# Module.net
KiCad netlist of a schematic drawn in Altium Designer
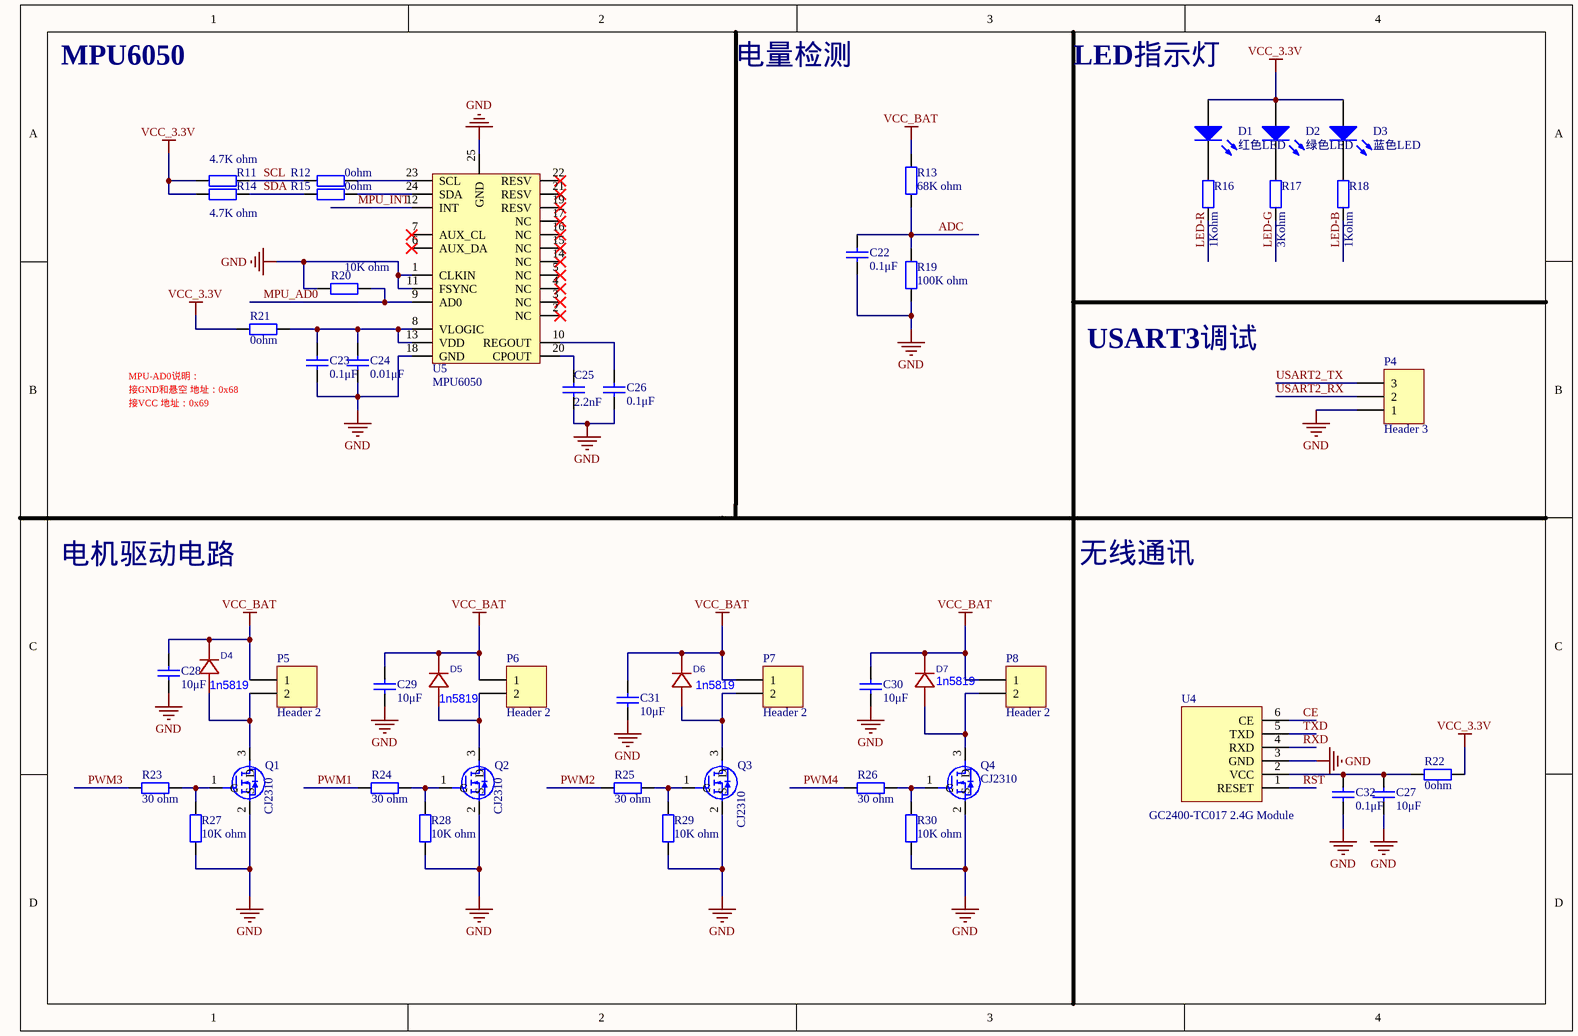
[diagram p0: Module.SchDoc]

(export (version "E")
  (design (tool "Eeschema 10.0.6"))
  (components
    (comp (ref "C22")
      (value "0.1μF")
      (footprint "0603C")
      (description "0.1μF_50V,X7R,±5%")
      (libsource (lib "Smart-Plane_1") (part "Cap_0.1μF_50V_0603"))
    )
    (comp (ref "C23")
      (value "0.1μF")
      (footprint "0603C")
      (description "0.1μF_50V,X7R,±5%")
      (libsource (lib "Smart-Plane_1") (part "Cap_0.1μF_50V_0603"))
    )
    (comp (ref "C24")
      (value "0.01μF")
      (footprint "0603C")
      (description "0.1μF_50V,X7R,±5%")
      (libsource (lib "Smart-Plane_1") (part "Cap_0.1μF_50V_0603"))
    )
    (comp (ref "C25")
      (value "2.2nF")
      (footprint "0603C")
      (description "10μF_35V,X5R,20%")
      (libsource (lib "Yang_Lib") (part "Cap_10μF_35V_0603"))
    )
    (comp (ref "C26")
      (value "0.1μF")
      (footprint "0603C")
      (description "0.1μF_50V,X7R,±5%")
      (libsource (lib "Smart-Plane_1") (part "Cap_0.1μF_50V_0603"))
    )
    (comp (ref "C27")
      (value "10μF")
      (footprint "0603C")
      (description "10μF_35V,X5R,20%")
      (libsource (lib "Yang_Lib") (part "Cap_10μF_35V_0603"))
    )
    (comp (ref "C28")
      (value "10μF")
      (footprint "0603C")
      (description "4.7μF_50V,±10%")
      (libsource (lib "Smart-Plane_1") (part "Cap_4.7μF_50V_0603"))
    )
    (comp (ref "C29")
      (value "10μF")
      (footprint "0603C")
      (description "4.7μF_50V,±10%")
      (libsource (lib "Smart-Plane_1") (part "Cap_4.7μF_50V_0603"))
    )
    (comp (ref "C30")
      (value "10μF")
      (footprint "0603C")
      (description "4.7μF_50V,±10%")
      (libsource (lib "Smart-Plane_1") (part "Cap_4.7μF_50V_0603"))
    )
    (comp (ref "C31")
      (value "10μF")
      (footprint "0603C")
      (description "4.7μF_50V,±10%")
      (libsource (lib "Smart-Plane_1") (part "Cap_4.7μF_50V_0603"))
    )
    (comp (ref "C32")
      (value "0.1μF")
      (footprint "0603C")
      (description "0.1μF_50V,X7R,±5%")
      (libsource (lib "Smart-Plane_1") (part "Cap_0.1μF_50V_0603"))
    )
    (comp (ref "D1")
      (value "红色LED")
      (footprint "0603LED")
      (description "蓝色LED")
      (libsource (lib "Smart-Plane_1") (part "蓝色LED"))
    )
    (comp (ref "D2")
      (value "绿色LED")
      (footprint "0603LED")
      (description "蓝色LED")
      (libsource (lib "Smart-Plane_1") (part "蓝色LED"))
    )
    (comp (ref "D3") (value "蓝色LED") (footprint "0603LED") (libsource (lib "Smart-Plane_1") (part "蓝色LED")))
    (comp (ref "D4")
      (value "1n5819")
      (footprint "0603R")
      (description "二极管配置:独立式;正向压降(Vf):600mV@200mA;直流反向耐压(Vr):40V;整流电流:350mA;")
      (fields (field (name "MANUFACTURER") "HXY MOSFET(华轩阳电子)") (field (name "MANUFACTURERPART") "1N5819WT"))
      (libsource (lib "Smart-Plane_1") (part "1n5819wt_c5451630"))
    )
    (comp (ref "D5")
      (value "1n5819")
      (footprint "0603R")
      (description "二极管配置:独立式;正向压降(Vf):600mV@200mA;直流反向耐压(Vr):40V;整流电流:350mA;")
      (fields (field (name "MANUFACTURER") "HXY MOSFET(华轩阳电子)") (field (name "MANUFACTURERPART") "1N5819WT"))
      (libsource (lib "Smart-Plane_1") (part "1n5819wt_c5451630"))
    )
    (comp (ref "D6")
      (value "1n5819")
      (footprint "0603R")
      (description "二极管配置:独立式;正向压降(Vf):600mV@200mA;直流反向耐压(Vr):40V;整流电流:350mA;")
      (fields (field (name "MANUFACTURER") "HXY MOSFET(华轩阳电子)") (field (name "MANUFACTURERPART") "1N5819WT"))
      (libsource (lib "Smart-Plane_1") (part "1n5819wt_c5451630"))
    )
    (comp (ref "D7")
      (value "1n5819")
      (footprint "0603R")
      (description "二极管配置:独立式;正向压降(Vf):600mV@200mA;直流反向耐压(Vr):40V;整流电流:350mA;")
      (fields (field (name "MANUFACTURER") "HXY MOSFET(华轩阳电子)") (field (name "MANUFACTURERPART") "1N5819WT"))
      (libsource (lib "Smart-Plane_1") (part "1n5819wt_c5451630"))
    )
    (comp (ref "P4")
      (value "Header 3")
      (footprint "HDR1X3")
      (description "Header, 3-Pin")
      (fields (field (name "PUBLISHER") "Altium Limited"))
      (libsource (lib "Smart-Plane_1") (part "Header 3"))
    )
    (comp (ref "P5")
      (value "Header 2")
      (footprint "HDR1X2")
      (description "Header, 2-Pin")
      (fields (field (name "PUBLISHER") "Altium Limited"))
      (libsource (lib "Miscellaneous Connectors") (part "Header 2"))
    )
    (comp (ref "P6")
      (value "Header 2")
      (footprint "HDR1X2")
      (description "Header, 2-Pin")
      (fields (field (name "PUBLISHER") "Altium Limited"))
      (libsource (lib "Miscellaneous Connectors") (part "Header 2"))
    )
    (comp (ref "P7")
      (value "Header 2")
      (footprint "HDR1X2")
      (description "Header, 2-Pin")
      (fields (field (name "PUBLISHER") "Altium Limited"))
      (libsource (lib "Miscellaneous Connectors") (part "Header 2"))
    )
    (comp (ref "P8")
      (value "Header 2")
      (footprint "HDR1X2")
      (description "Header, 2-Pin")
      (fields (field (name "PUBLISHER") "Altium Limited"))
      (libsource (lib "Miscellaneous Connectors") (part "Header 2"))
    )
    (comp (ref "Q1") (value "CJ2310") (footprint "SOT23-3") (libsource (lib "Yang_Lib") (part "CJ2310")))
    (comp (ref "Q2") (value "CJ2310") (footprint "SOT23-3") (libsource (lib "Yang_Lib") (part "CJ2310")))
    (comp (ref "Q3") (value "CJ2310") (footprint "SOT23-3") (libsource (lib "Yang_Lib") (part "CJ2310")))
    (comp (ref "Q4") (value "CJ2310") (footprint "SOT23-3") (libsource (lib "Yang_Lib") (part "CJ2310")))
    (comp (ref "R11")
      (value "4.7K ohm")
      (footprint "0603R")
      (description "4.7K ohm,1%")
      (libsource (lib "Yang_Lib") (part "Res_4.7K ohm_0603"))
    )
    (comp (ref "R12")
      (value "0ohm")
      (footprint "0603R")
      (description "120 ohm_5%")
      (libsource (lib "Yang_Lib") (part "Res_120ohm_0603"))
    )
    (comp (ref "R13")
      (value "68K ohm")
      (footprint "0603R")
      (description "200K ohm,1%")
      (libsource (lib "Yang_Lib") (part "Res_200K ohm_0603"))
    )
    (comp (ref "R14")
      (value "4.7K ohm")
      (footprint "0603R")
      (description "4.7K ohm,1%")
      (libsource (lib "Yang_Lib") (part "Res_4.7K ohm_0603"))
    )
    (comp (ref "R15")
      (value "0ohm")
      (footprint "0603R")
      (description "120 ohm_5%")
      (libsource (lib "Yang_Lib") (part "Res_120ohm_0603"))
    )
    (comp (ref "R16")
      (value "1Kohm")
      (footprint "0603R")
      (description "510 ohm,1%")
      (libsource (lib "Yang_Lib") (part "Res_510ohm_0603"))
    )
    (comp (ref "R17")
      (value "3Kohm")
      (footprint "0603R")
      (description "510 ohm,1%")
      (libsource (lib "Yang_Lib") (part "Res_510ohm_0603"))
    )
    (comp (ref "R18")
      (value "1Kohm")
      (footprint "0603R")
      (description "510 ohm,1%")
      (libsource (lib "Yang_Lib") (part "Res_510ohm_0603"))
    )
    (comp (ref "R19")
      (value "100K ohm")
      (footprint "0603R")
      (description "68K ohm,1%")
      (libsource (lib "Yang_Lib") (part "Res_68K ohm_0603"))
    )
    (comp (ref "R20")
      (value "10K ohm")
      (footprint "0603R")
      (description "10K ohm,1%")
      (libsource (lib "") (part "Res_10K ohm_0603_1"))
    )
    (comp (ref "R21")
      (value "0ohm")
      (footprint "0603R")
      (description "24K ohm,1%")
      (libsource (lib "Yang_Lib") (part "Res_24K ohm_0603"))
    )
    (comp (ref "R22")
      (value "0ohm")
      (footprint "0603R")
      (description "24K ohm,1%")
      (libsource (lib "Yang_Lib") (part "Res_24K ohm_0603"))
    )
    (comp (ref "R23")
      (value "30 ohm")
      (footprint "0603R")
      (description "100 ohm_5%")
      (libsource (lib "Yang_Lib") (part "Res_100ohm_0603"))
    )
    (comp (ref "R24")
      (value "30 ohm")
      (footprint "0603R")
      (description "100 ohm_5%")
      (libsource (lib "Yang_Lib") (part "Res_100ohm_0603"))
    )
    (comp (ref "R25")
      (value "30 ohm")
      (footprint "0603R")
      (description "100 ohm_5%")
      (libsource (lib "Yang_Lib") (part "Res_100ohm_0603"))
    )
    (comp (ref "R26")
      (value "30 ohm")
      (footprint "0603R")
      (description "100 ohm_5%")
      (libsource (lib "Yang_Lib") (part "Res_100ohm_0603"))
    )
    (comp (ref "R27")
      (value "10K ohm")
      (footprint "0603R")
      (description "10K ohm,1%")
      (libsource (lib "Smart-Plane_1") (part "Res_10K ohm_0603"))
    )
    (comp (ref "R28")
      (value "10K ohm")
      (footprint "0603R")
      (description "10K ohm,1%")
      (libsource (lib "Smart-Plane_1") (part "Res_10K ohm_0603"))
    )
    (comp (ref "R29")
      (value "10K ohm")
      (footprint "0603R")
      (description "10K ohm,1%")
      (libsource (lib "Smart-Plane_1") (part "Res_10K ohm_0603"))
    )
    (comp (ref "R30")
      (value "10K ohm")
      (footprint "0603R")
      (description "10K ohm,1%")
      (libsource (lib "Smart-Plane_1") (part "Res_10K ohm_0603"))
    )
    (comp (ref "U4")
      (value "GC2400-TC017 2.4G Module")
      (footprint "2.4G-Serial port")
      (description "2.4G_转串口")
      (libsource (lib "Smart-Plane_1") (part "2.4G_转串口"))
    )
    (comp (ref "U5") (value "MPU6050") (footprint "QFN24") (libsource (lib "Yang_Lib") (part "MPU6050")))
  )
  (nets
    (net (code "1") (name "/ADC") (class "Default")
      (node (ref "C22") (pin "2") (pinfunction "2_2") (pintype "passive"))
      (node (ref "R13") (pin "1") (pinfunction "1_1") (pintype "passive"))
      (node (ref "R19") (pin "2") (pinfunction "2_2") (pintype "passive"))
    )
    (net (code "2") (name "/CE") (class "Default")
      (node (ref "U4") (pin "6") (pinfunction "CE_6") (pintype "passive"))
    )
    (net (code "3") (name "/LED-B") (class "Default")
      (node (ref "R18") (pin "1") (pinfunction "1_1") (pintype "passive"))
    )
    (net (code "4") (name "/LED-G") (class "Default")
      (node (ref "R17") (pin "1") (pinfunction "1_1") (pintype "passive"))
    )
    (net (code "5") (name "/LED-R") (class "Default")
      (node (ref "R16") (pin "1") (pinfunction "1_1") (pintype "passive"))
    )
    (net (code "6") (name "/MPU_AD0") (class "Default")
      (node (ref "R20") (pin "2") (pinfunction "2_2") (pintype "passive"))
      (node (ref "U5") (pin "9") (pinfunction "AD0_9") (pintype "passive"))
    )
    (net (code "7") (name "/MPU_INT") (class "Default")
      (node (ref "U5") (pin "12") (pinfunction "INT_12") (pintype "passive"))
    )
    (net (code "8") (name "/PWM1") (class "Default")
      (node (ref "R24") (pin "1") (pinfunction "1_1") (pintype "passive"))
    )
    (net (code "9") (name "/PWM2") (class "Default")
      (node (ref "R25") (pin "1") (pinfunction "1_1") (pintype "passive"))
    )
    (net (code "10") (name "/PWM3") (class "Default")
      (node (ref "R23") (pin "1") (pinfunction "1_1") (pintype "passive"))
    )
    (net (code "11") (name "/PWM4") (class "Default")
      (node (ref "R26") (pin "1") (pinfunction "1_1") (pintype "passive"))
    )
    (net (code "12") (name "/RST") (class "Default")
      (node (ref "U4") (pin "1") (pinfunction "RESET_1") (pintype "passive"))
    )
    (net (code "13") (name "/RXD") (class "Default")
      (node (ref "U4") (pin "4") (pinfunction "RXD_4") (pintype "passive"))
    )
    (net (code "14") (name "/SCL") (class "Default")
      (node (ref "R11") (pin "2") (pinfunction "2_2") (pintype "passive"))
      (node (ref "R12") (pin "1") (pinfunction "1_1") (pintype "passive"))
    )
    (net (code "15") (name "/SDA") (class "Default")
      (node (ref "R14") (pin "2") (pinfunction "2_2") (pintype "passive"))
      (node (ref "R15") (pin "1") (pinfunction "1_1") (pintype "passive"))
    )
    (net (code "16") (name "/TXD") (class "Default")
      (node (ref "U4") (pin "5") (pinfunction "TXD_5") (pintype "passive"))
    )
    (net (code "17") (name "/USART2_RX") (class "Default")
      (node (ref "P4") (pin "2") (pinfunction "2_2") (pintype "passive"))
    )
    (net (code "18") (name "/USART2_TX") (class "Default")
      (node (ref "P4") (pin "3") (pinfunction "3_3") (pintype "passive"))
    )
    (net (code "19") (name "GND") (class "Default")
      (node (ref "C22") (pin "1") (pinfunction "1_1") (pintype "passive"))
      (node (ref "C23") (pin "1") (pinfunction "1_1") (pintype "passive"))
      (node (ref "C24") (pin "1") (pinfunction "1_1") (pintype "passive"))
      (node (ref "C25") (pin "1") (pinfunction "1_1") (pintype "passive"))
      (node (ref "C26") (pin "1") (pinfunction "1_1") (pintype "passive"))
      (node (ref "C27") (pin "1") (pinfunction "1_1") (pintype "passive"))
      (node (ref "C28") (pin "1") (pinfunction "1_1") (pintype "passive"))
      (node (ref "C29") (pin "1") (pinfunction "1_1") (pintype "passive"))
      (node (ref "C30") (pin "1") (pinfunction "1_1") (pintype "passive"))
      (node (ref "C31") (pin "1") (pinfunction "1_1") (pintype "passive"))
      (node (ref "C32") (pin "1") (pinfunction "1_1") (pintype "passive"))
      (node (ref "P4") (pin "1") (pinfunction "1_1") (pintype "passive"))
      (node (ref "Q1") (pin "2") (pinfunction "S_2") (pintype "passive"))
      (node (ref "Q2") (pin "2") (pinfunction "S_2") (pintype "passive"))
      (node (ref "Q3") (pin "2") (pinfunction "S_2") (pintype "passive"))
      (node (ref "Q4") (pin "2") (pinfunction "S_2") (pintype "passive"))
      (node (ref "R19") (pin "1") (pinfunction "1_1") (pintype "passive"))
      (node (ref "R20") (pin "1") (pinfunction "1_1") (pintype "passive"))
      (node (ref "R27") (pin "1") (pinfunction "1_1") (pintype "passive"))
      (node (ref "R28") (pin "1") (pinfunction "1_1") (pintype "passive"))
      (node (ref "R29") (pin "1") (pinfunction "1_1") (pintype "passive"))
      (node (ref "R30") (pin "1") (pinfunction "1_1") (pintype "passive"))
      (node (ref "U4") (pin "3") (pinfunction "GND_3") (pintype "passive"))
      (node (ref "U5") (pin "1") (pinfunction "CLKIN_1") (pintype "passive"))
      (node (ref "U5") (pin "11") (pinfunction "FSYNC_11") (pintype "passive"))
      (node (ref "U5") (pin "18") (pinfunction "GND_18") (pintype "passive"))
      (node (ref "U5") (pin "25") (pinfunction "GND_25") (pintype "passive"))
    )
    (net (code "20") (name "Net-(D1-K)") (class "Default")
      (node (ref "D1") (pin "2") (pinfunction "K_2") (pintype "passive"))
      (node (ref "R16") (pin "2") (pinfunction "2_2") (pintype "passive"))
    )
    (net (code "21") (name "Net-(D2-K)") (class "Default")
      (node (ref "D2") (pin "2") (pinfunction "K_2") (pintype "passive"))
      (node (ref "R17") (pin "2") (pinfunction "2_2") (pintype "passive"))
    )
    (net (code "22") (name "Net-(D3-K)") (class "Default")
      (node (ref "D3") (pin "2") (pinfunction "K_2") (pintype "passive"))
      (node (ref "R18") (pin "2") (pinfunction "2_2") (pintype "passive"))
    )
    (net (code "23") (name "Net-(D4-A)") (class "Default")
      (node (ref "D4") (pin "2") (pinfunction "A_2") (pintype "passive"))
      (node (ref "P5") (pin "2") (pinfunction "2_2") (pintype "passive"))
      (node (ref "Q1") (pin "3") (pinfunction "D_3") (pintype "passive"))
    )
    (net (code "24") (name "Net-(D5-A)") (class "Default")
      (node (ref "D5") (pin "2") (pinfunction "A_2") (pintype "passive"))
      (node (ref "P6") (pin "2") (pinfunction "2_2") (pintype "passive"))
      (node (ref "Q2") (pin "3") (pinfunction "D_3") (pintype "passive"))
    )
    (net (code "25") (name "Net-(D6-A)") (class "Default")
      (node (ref "D6") (pin "2") (pinfunction "A_2") (pintype "passive"))
      (node (ref "P7") (pin "2") (pinfunction "2_2") (pintype "passive"))
      (node (ref "Q3") (pin "3") (pinfunction "D_3") (pintype "passive"))
    )
    (net (code "26") (name "Net-(D7-A)") (class "Default")
      (node (ref "D7") (pin "2") (pinfunction "A_2") (pintype "passive"))
      (node (ref "P8") (pin "2") (pinfunction "2_2") (pintype "passive"))
      (node (ref "Q4") (pin "3") (pinfunction "D_3") (pintype "passive"))
    )
    (net (code "27") (name "Net-(Q1-G)") (class "Default")
      (node (ref "Q1") (pin "1") (pinfunction "G_1") (pintype "passive"))
      (node (ref "R23") (pin "2") (pinfunction "2_2") (pintype "passive"))
      (node (ref "R27") (pin "2") (pinfunction "2_2") (pintype "passive"))
    )
    (net (code "28") (name "Net-(Q2-G)") (class "Default")
      (node (ref "Q2") (pin "1") (pinfunction "G_1") (pintype "passive"))
      (node (ref "R24") (pin "2") (pinfunction "2_2") (pintype "passive"))
      (node (ref "R28") (pin "2") (pinfunction "2_2") (pintype "passive"))
    )
    (net (code "29") (name "Net-(Q3-G)") (class "Default")
      (node (ref "Q3") (pin "1") (pinfunction "G_1") (pintype "passive"))
      (node (ref "R25") (pin "2") (pinfunction "2_2") (pintype "passive"))
      (node (ref "R29") (pin "2") (pinfunction "2_2") (pintype "passive"))
    )
    (net (code "30") (name "Net-(Q4-G)") (class "Default")
      (node (ref "Q4") (pin "1") (pinfunction "G_1") (pintype "passive"))
      (node (ref "R26") (pin "2") (pinfunction "2_2") (pintype "passive"))
      (node (ref "R30") (pin "2") (pinfunction "2_2") (pintype "passive"))
    )
    (net (code "31") (name "Net-(U4-VCC)") (class "Default")
      (node (ref "C27") (pin "2") (pinfunction "2_2") (pintype "passive"))
      (node (ref "C32") (pin "2") (pinfunction "2_2") (pintype "passive"))
      (node (ref "R22") (pin "2") (pinfunction "2_2") (pintype "passive"))
      (node (ref "U4") (pin "2") (pinfunction "VCC_2") (pintype "passive"))
    )
    (net (code "32") (name "Net-(U5-CPOUT)") (class "Default")
      (node (ref "C25") (pin "2") (pinfunction "2_2") (pintype "passive"))
      (node (ref "U5") (pin "20") (pinfunction "CPOUT_20") (pintype "passive"))
    )
    (net (code "33") (name "Net-(U5-REGOUT)") (class "Default")
      (node (ref "C26") (pin "2") (pinfunction "2_2") (pintype "passive"))
      (node (ref "U5") (pin "10") (pinfunction "REGOUT_10") (pintype "passive"))
    )
    (net (code "34") (name "Net-(U5-SCL)") (class "Default")
      (node (ref "R12") (pin "2") (pinfunction "2_2") (pintype "passive"))
      (node (ref "U5") (pin "23") (pinfunction "SCL_23") (pintype "passive"))
    )
    (net (code "35") (name "Net-(U5-SDA)") (class "Default")
      (node (ref "R15") (pin "2") (pinfunction "2_2") (pintype "passive"))
      (node (ref "U5") (pin "24") (pinfunction "SDA_24") (pintype "passive"))
    )
    (net (code "36") (name "Net-(U5-VDD)") (class "Default")
      (node (ref "C23") (pin "2") (pinfunction "2_2") (pintype "passive"))
      (node (ref "C24") (pin "2") (pinfunction "2_2") (pintype "passive"))
      (node (ref "R21") (pin "1") (pinfunction "1_1") (pintype "passive"))
      (node (ref "U5") (pin "13") (pinfunction "VDD_13") (pintype "passive"))
      (node (ref "U5") (pin "8") (pinfunction "VLOGIC_8") (pintype "passive"))
    )
    (net (code "37") (name "VCC_3.3V") (class "Default")
      (node (ref "D1") (pin "1") (pinfunction "A_1") (pintype "passive"))
      (node (ref "D2") (pin "1") (pinfunction "A_1") (pintype "passive"))
      (node (ref "D3") (pin "1") (pinfunction "A_1") (pintype "passive"))
      (node (ref "R11") (pin "1") (pinfunction "1_1") (pintype "passive"))
      (node (ref "R14") (pin "1") (pinfunction "1_1") (pintype "passive"))
      (node (ref "R21") (pin "2") (pinfunction "2_2") (pintype "passive"))
      (node (ref "R22") (pin "1") (pinfunction "1_1") (pintype "passive"))
    )
    (net (code "38") (name "VCC_BAT") (class "Default")
      (node (ref "C28") (pin "2") (pinfunction "2_2") (pintype "passive"))
      (node (ref "C29") (pin "2") (pinfunction "2_2") (pintype "passive"))
      (node (ref "C30") (pin "2") (pinfunction "2_2") (pintype "passive"))
      (node (ref "C31") (pin "2") (pinfunction "2_2") (pintype "passive"))
      (node (ref "D4") (pin "1") (pinfunction "K_1") (pintype "passive"))
      (node (ref "D5") (pin "1") (pinfunction "K_1") (pintype "passive"))
      (node (ref "D6") (pin "1") (pinfunction "K_1") (pintype "passive"))
      (node (ref "D7") (pin "1") (pinfunction "K_1") (pintype "passive"))
      (node (ref "P5") (pin "1") (pinfunction "1_1") (pintype "passive"))
      (node (ref "P6") (pin "1") (pinfunction "1_1") (pintype "passive"))
      (node (ref "P7") (pin "1") (pinfunction "1_1") (pintype "passive"))
      (node (ref "P8") (pin "1") (pinfunction "1_1") (pintype "passive"))
      (node (ref "R13") (pin "2") (pinfunction "2_2") (pintype "passive"))
    )
    (net (code "39") (name "unconnected-(U5-AUX_CL-Pad7)") (class "Default")
      (node (ref "U5") (pin "7") (pinfunction "AUX_CL_7") (pintype "passive+no_connect"))
    )
    (net (code "40") (name "unconnected-(U5-AUX_DA-Pad6)") (class "Default")
      (node (ref "U5") (pin "6") (pinfunction "AUX_DA_6") (pintype "passive+no_connect"))
    )
    (net (code "41") (name "unconnected-(U5-NC-Pad2)") (class "Default")
      (node (ref "U5") (pin "2") (pinfunction "NC_2") (pintype "passive+no_connect"))
    )
    (net (code "42") (name "unconnected-(U5-NC-Pad3)") (class "Default")
      (node (ref "U5") (pin "3") (pinfunction "NC_3") (pintype "passive+no_connect"))
    )
    (net (code "43") (name "unconnected-(U5-NC-Pad4)") (class "Default")
      (node (ref "U5") (pin "4") (pinfunction "NC_4") (pintype "passive+no_connect"))
    )
    (net (code "44") (name "unconnected-(U5-NC-Pad5)") (class "Default")
      (node (ref "U5") (pin "5") (pinfunction "NC_5") (pintype "passive+no_connect"))
    )
    (net (code "45") (name "unconnected-(U5-NC-Pad14)") (class "Default")
      (node (ref "U5") (pin "14") (pinfunction "NC_14") (pintype "passive+no_connect"))
    )
    (net (code "46") (name "unconnected-(U5-NC-Pad15)") (class "Default")
      (node (ref "U5") (pin "15") (pinfunction "NC_15") (pintype "passive+no_connect"))
    )
    (net (code "47") (name "unconnected-(U5-NC-Pad16)") (class "Default")
      (node (ref "U5") (pin "16") (pinfunction "NC_16") (pintype "passive+no_connect"))
    )
    (net (code "48") (name "unconnected-(U5-NC-Pad17)") (class "Default")
      (node (ref "U5") (pin "17") (pinfunction "NC_17") (pintype "passive+no_connect"))
    )
    (net (code "49") (name "unconnected-(U5-RESV-Pad19)") (class "Default")
      (node (ref "U5") (pin "19") (pinfunction "RESV_19") (pintype "passive+no_connect"))
    )
    (net (code "50") (name "unconnected-(U5-RESV-Pad21)") (class "Default")
      (node (ref "U5") (pin "21") (pinfunction "RESV_21") (pintype "passive+no_connect"))
    )
    (net (code "51") (name "unconnected-(U5-RESV-Pad22)") (class "Default")
      (node (ref "U5") (pin "22") (pinfunction "RESV_22") (pintype "passive+no_connect"))
    )
  )
)
